# BMS_Main_RevC1.net
KiCad netlist of a schematic drawn in EAGLE
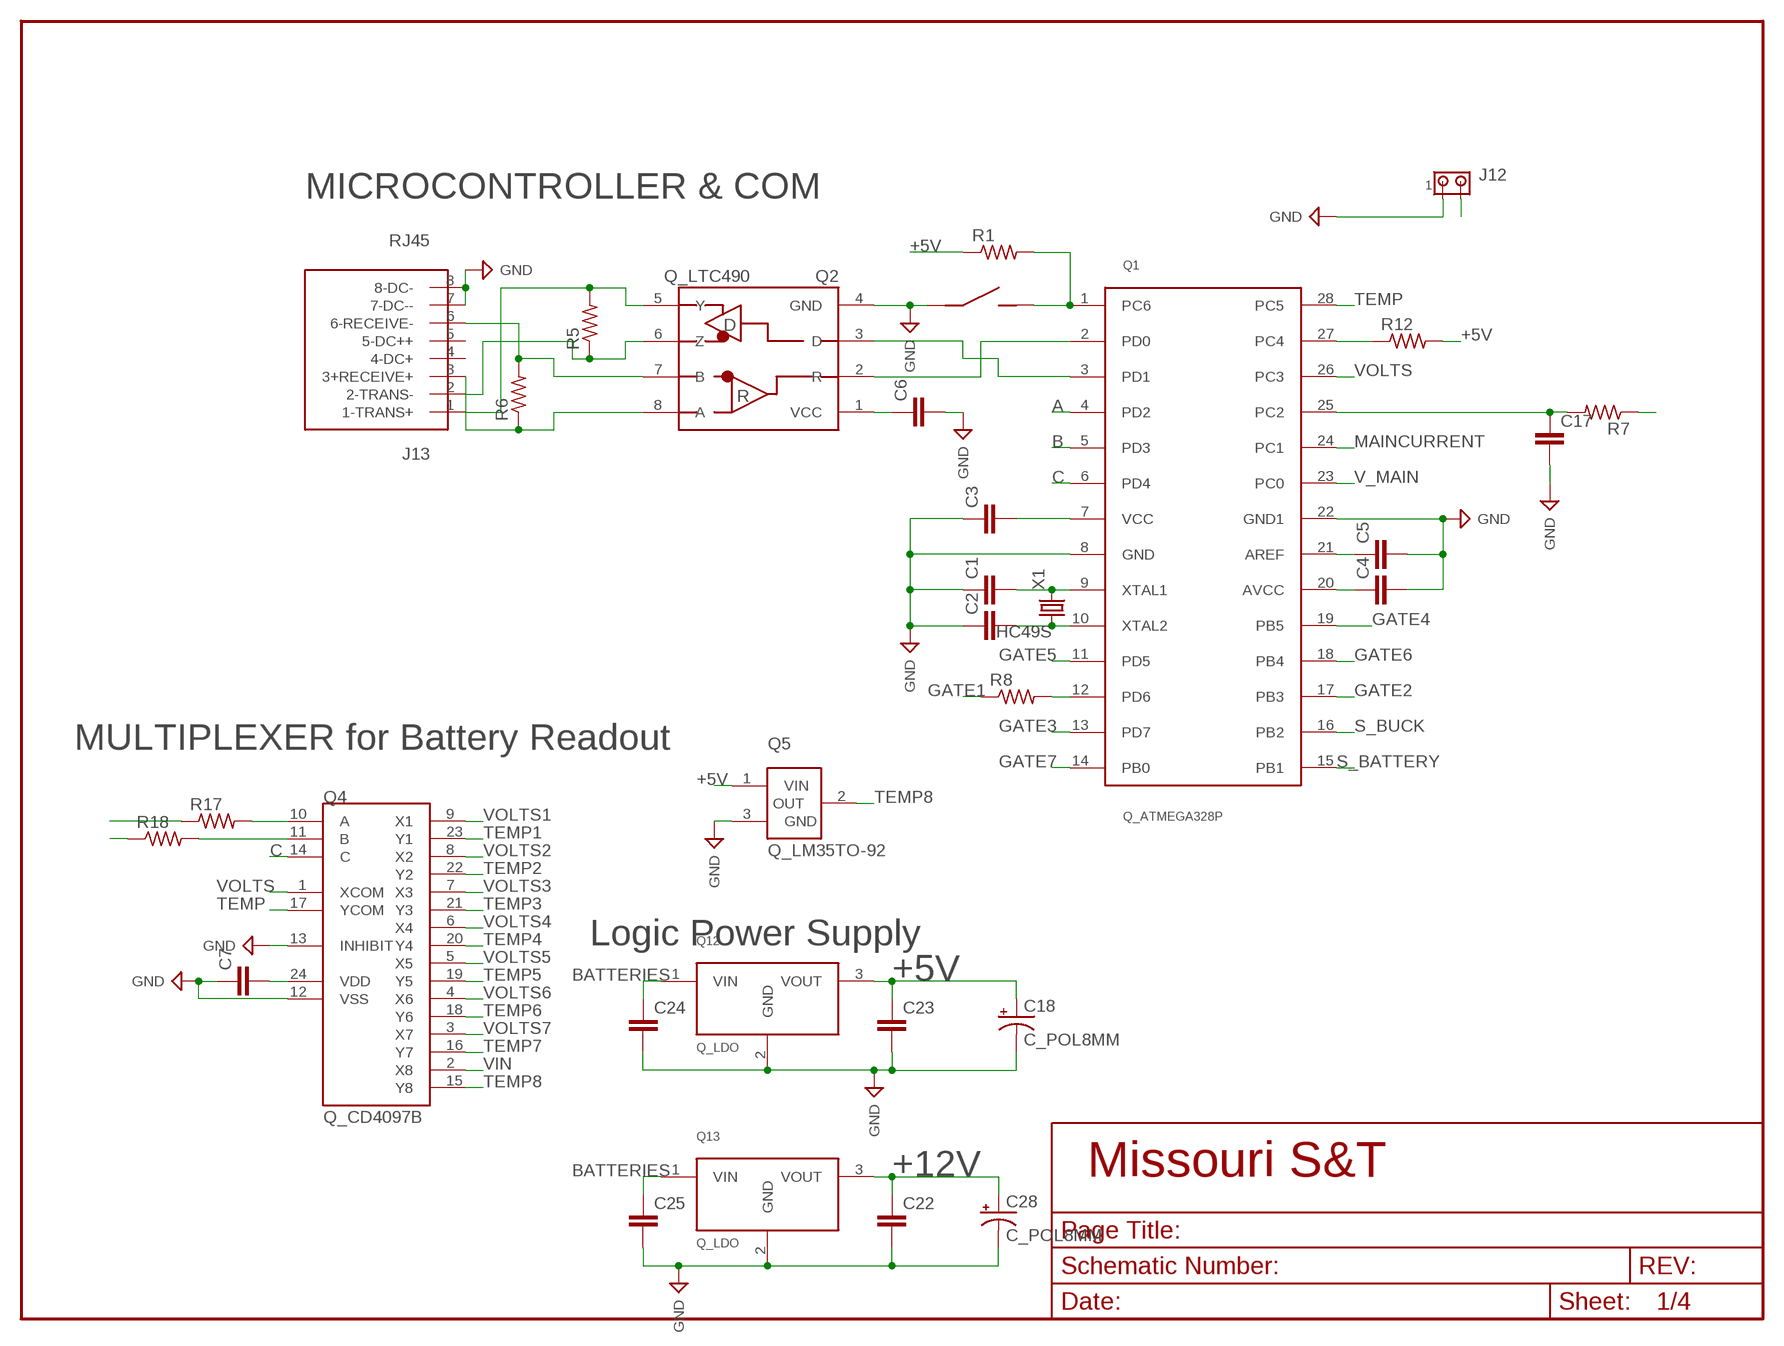
[diagram p0: schematic, sheet 1]
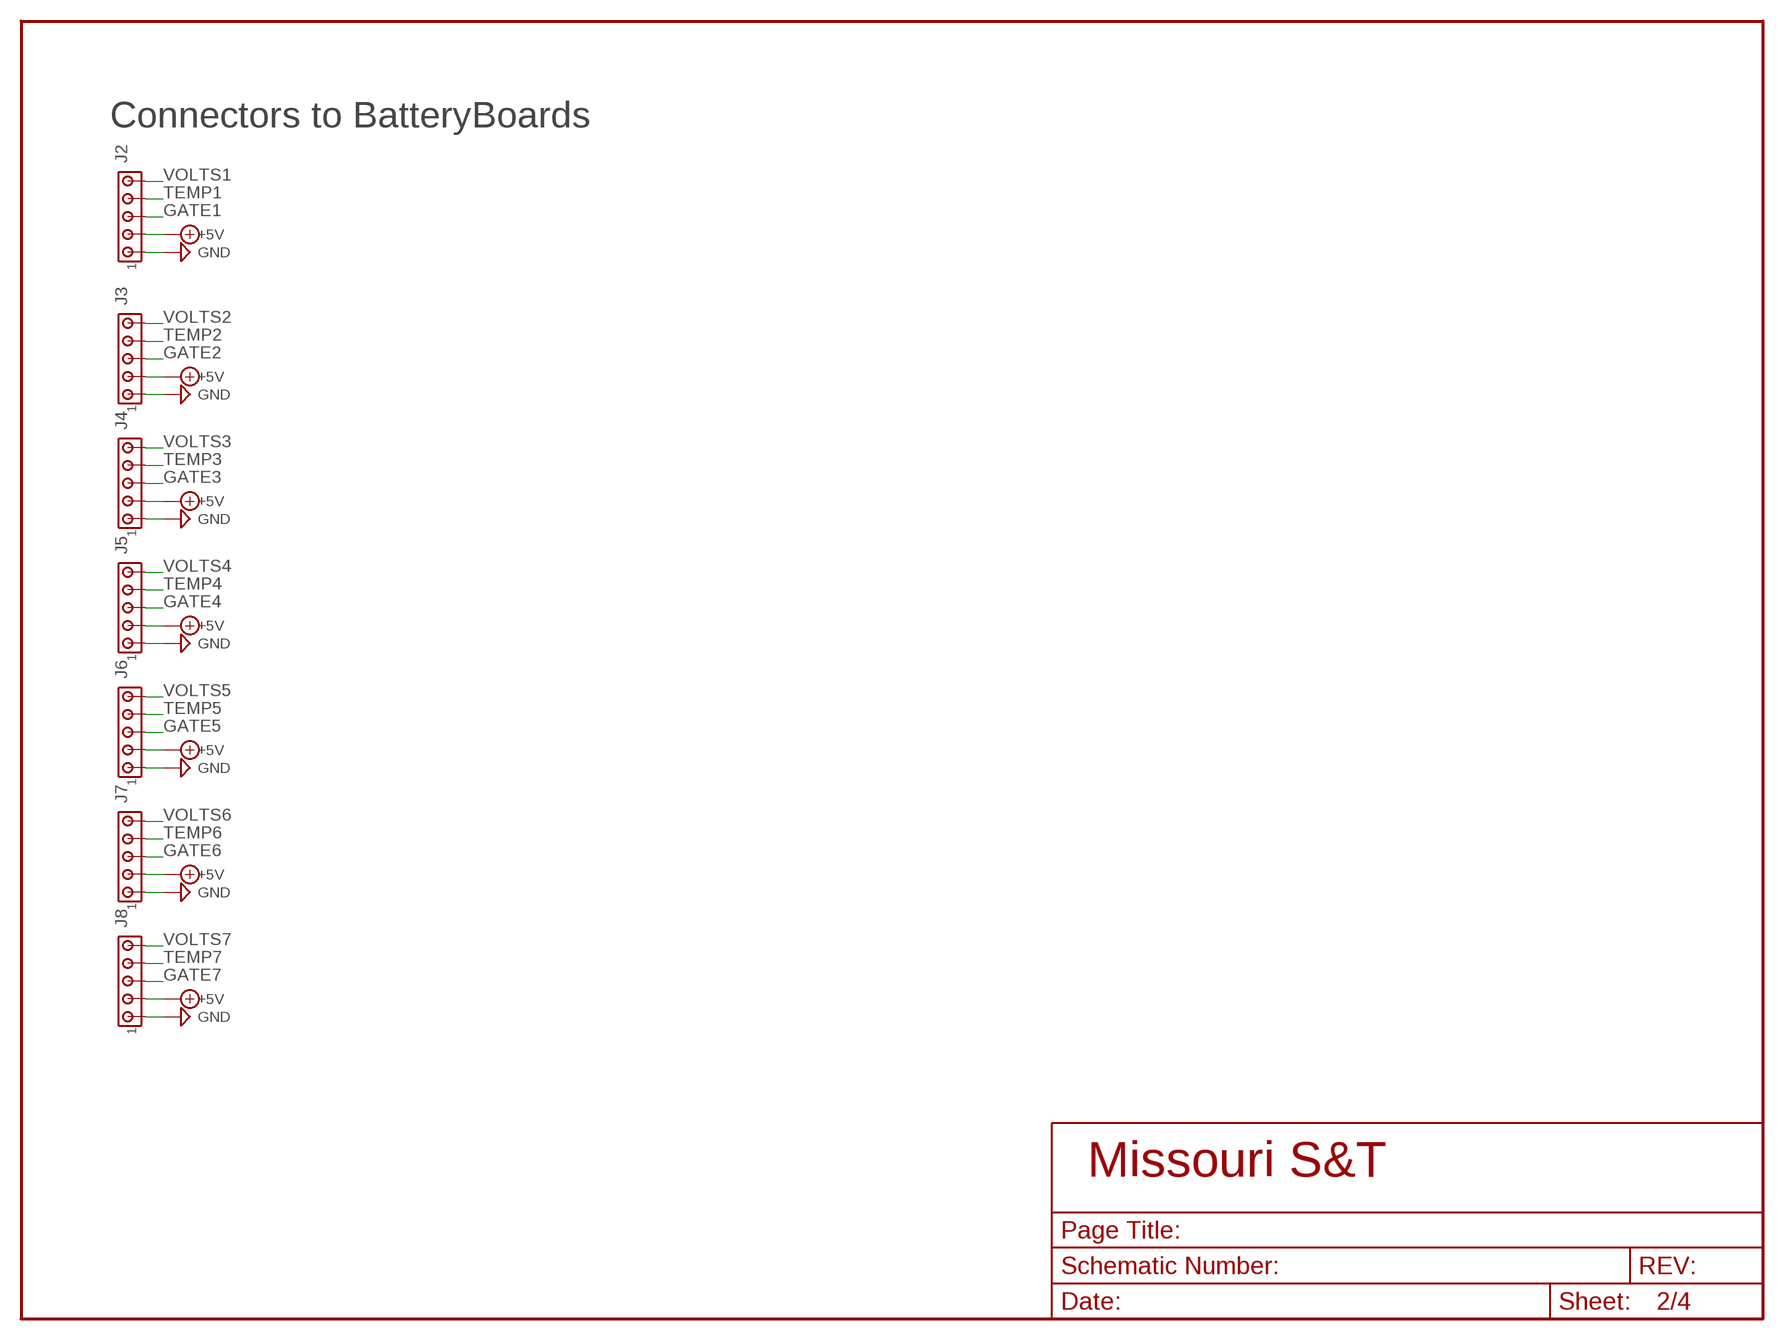
[diagram p1: schematic, sheet 2]
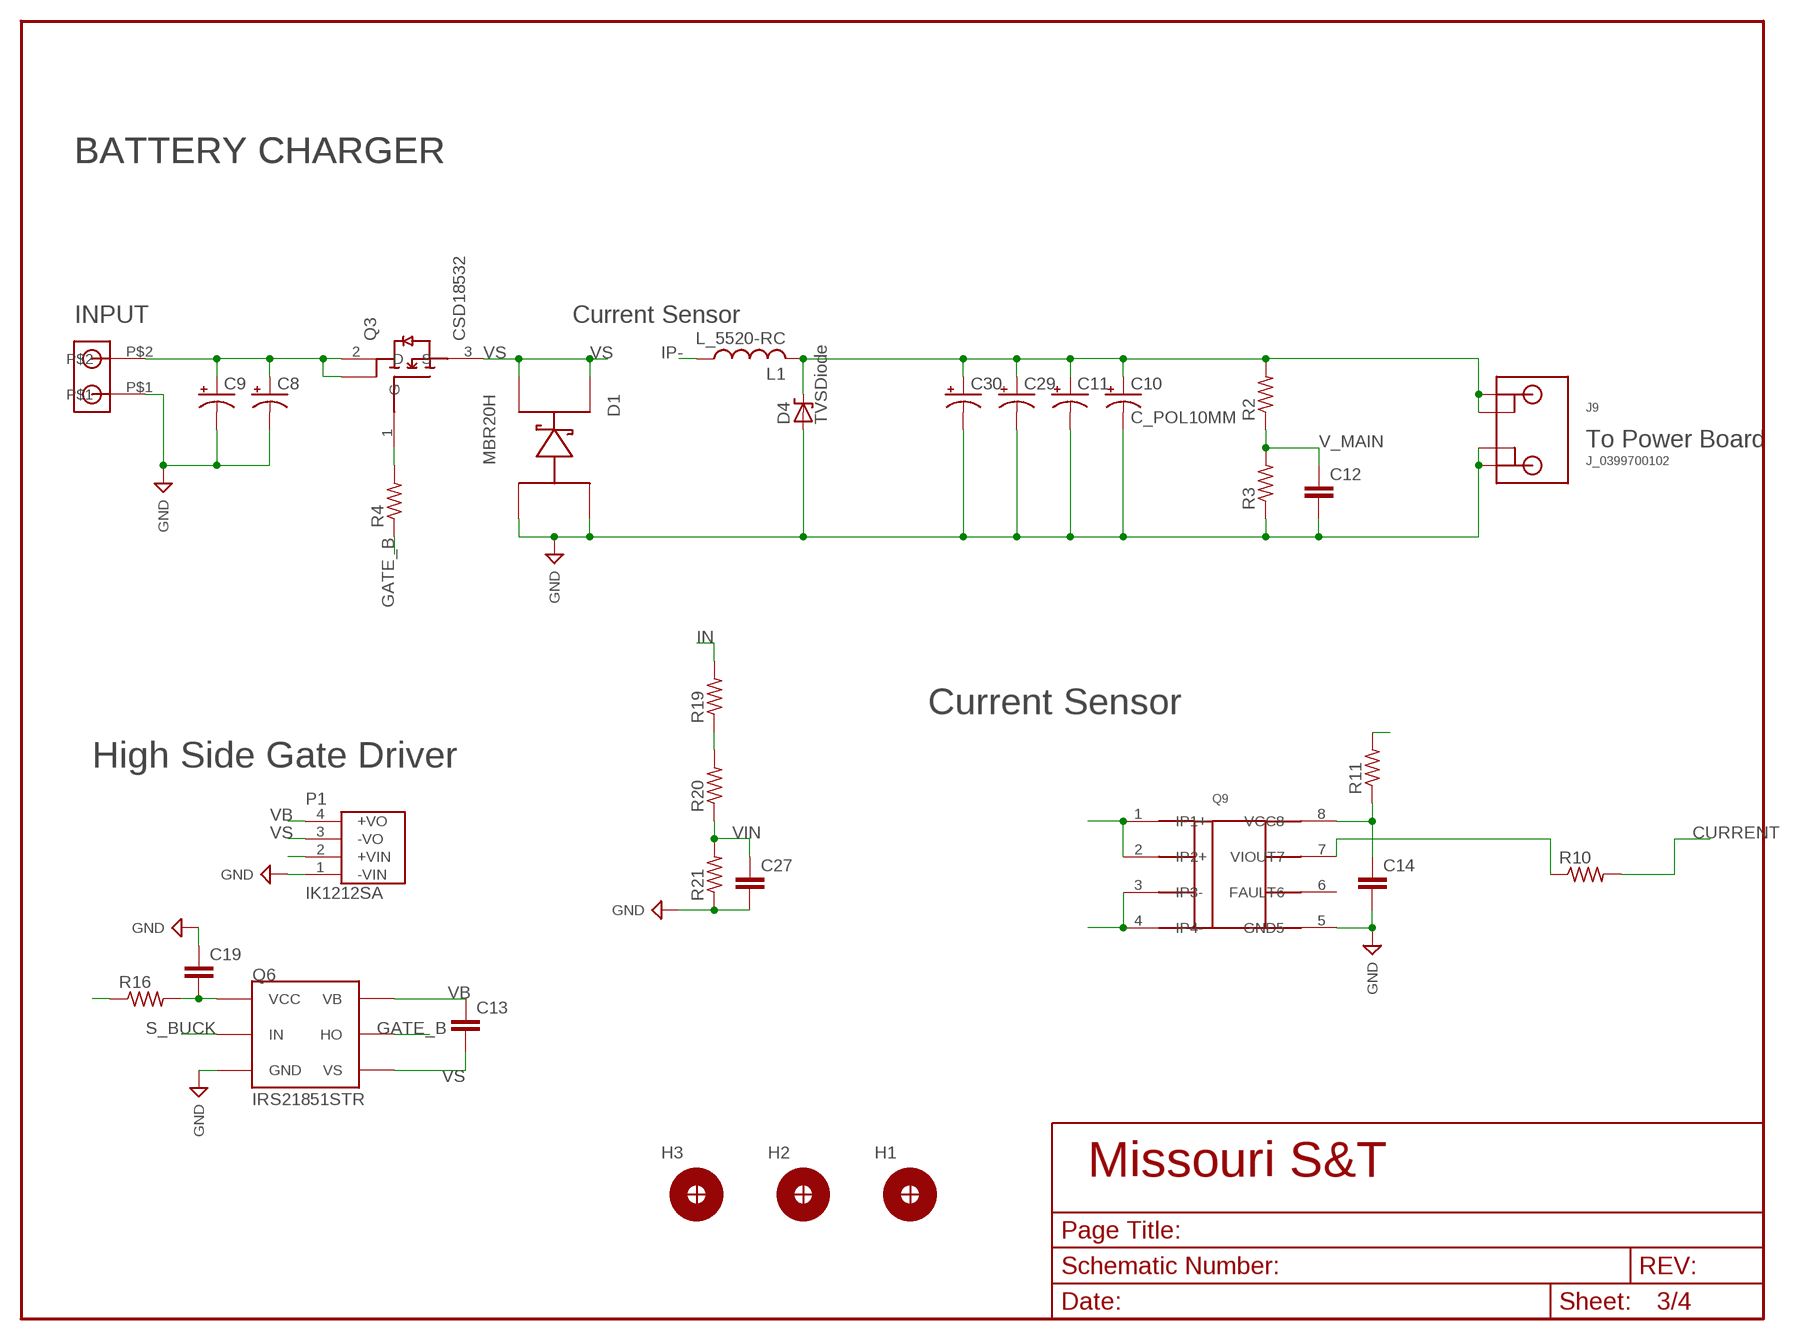
[diagram p2: schematic, sheet 3]
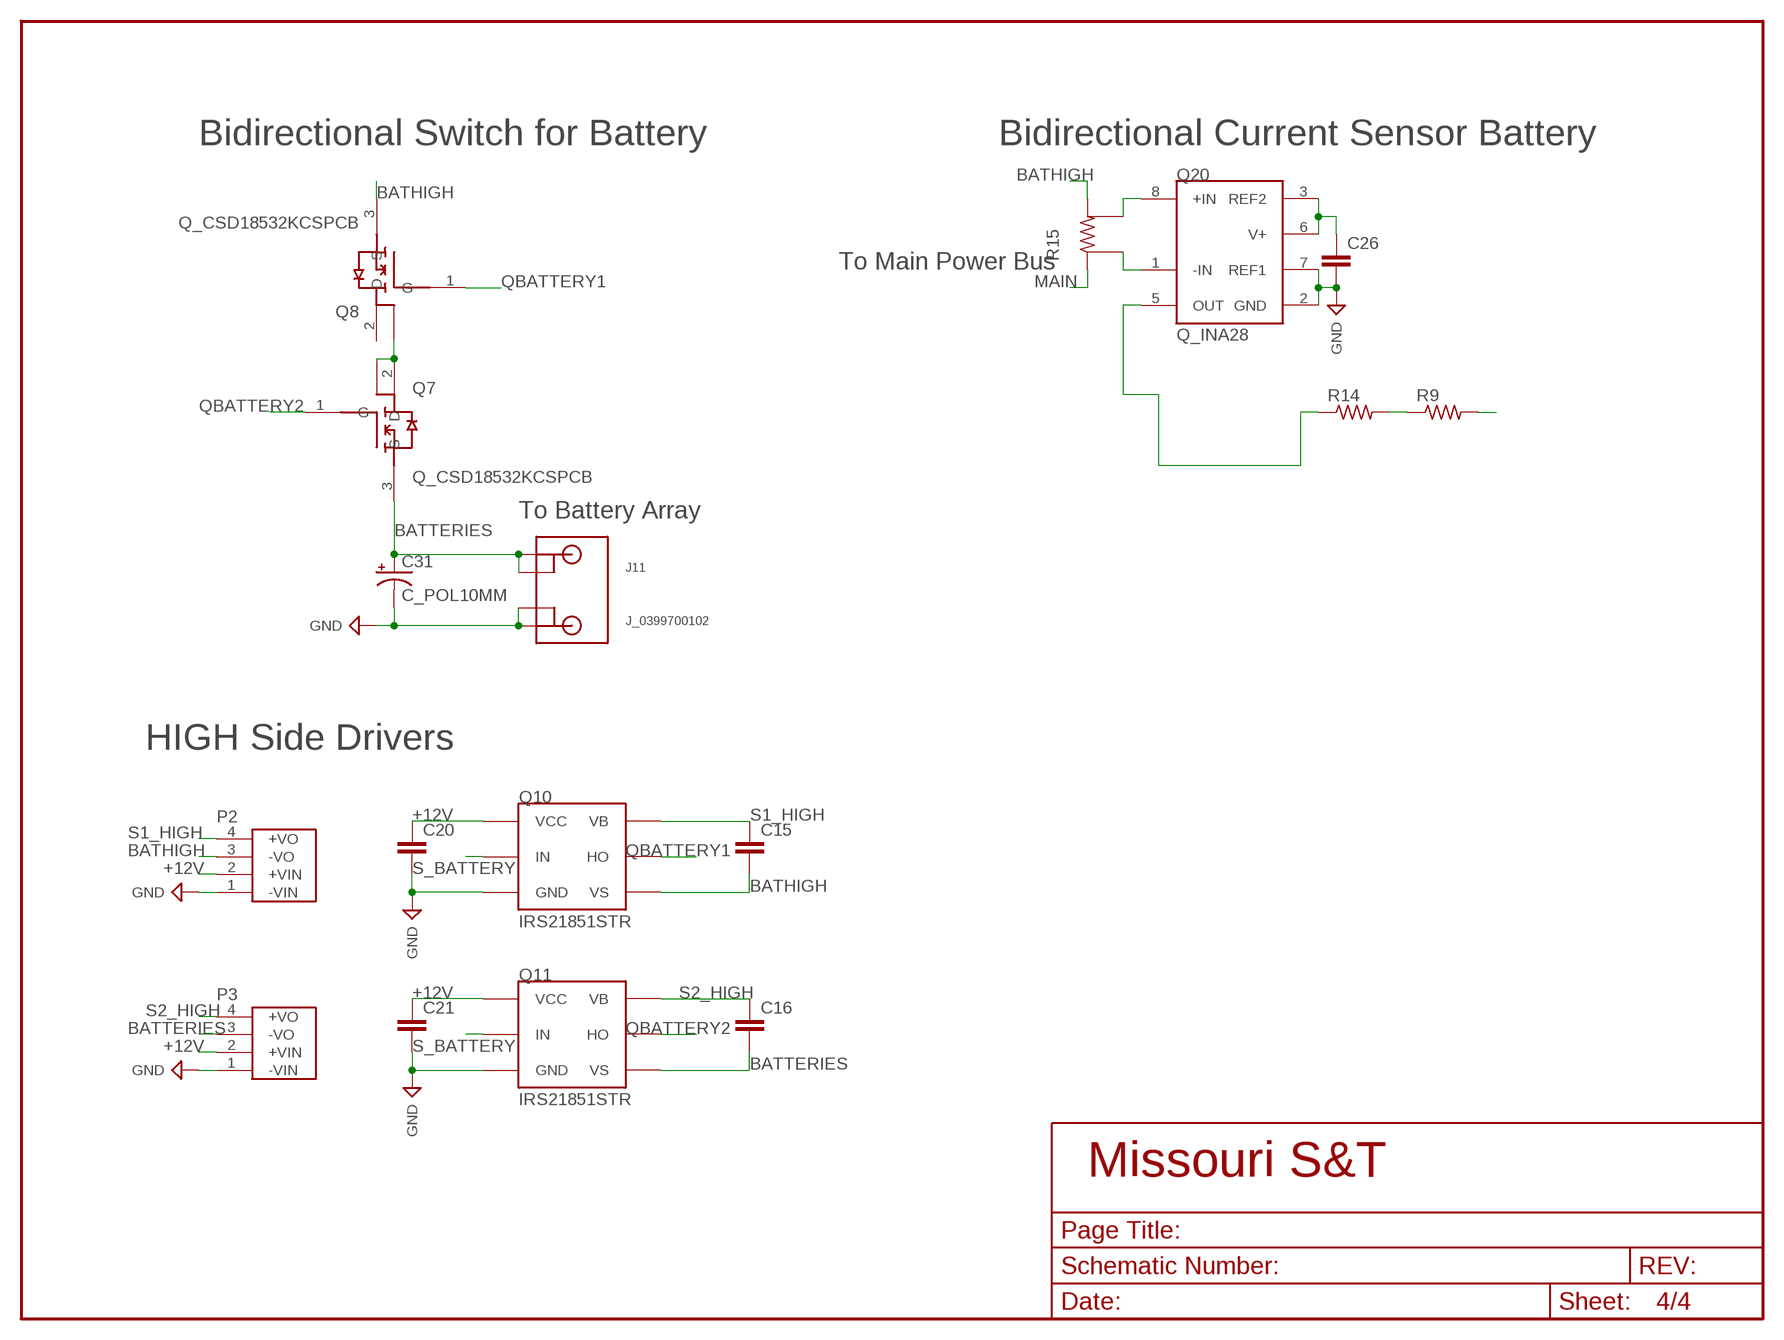
[diagram p3: schematic, sheet 4]

(export (version "E")
  (design (tool "Eeschema 10.0.6"))
  (components
    (comp (ref "C8")
      (value "C_POL10MM")
      (footprint "eagle-import:C_10MM")
      (libsource (lib "eagle-import") (part "C_POL10MM"))
    )
    (comp (ref "C9")
      (value "C_POL10MM")
      (footprint "eagle-import:C_10MM")
      (libsource (lib "eagle-import") (part "C_POL10MM"))
    )
    (comp (ref "C10")
      (value "C_POL10MM")
      (footprint "eagle-import:C_10MM")
      (libsource (lib "eagle-import") (part "C_POL10MM"))
    )
    (comp (ref "C11")
      (value "C_POL10MM")
      (footprint "eagle-import:C_10MM")
      (libsource (lib "eagle-import") (part "C_POL10MM"))
    )
    (comp (ref "C12")
      (value "C_CAP_1206")
      (footprint "eagle-import:C_1206")
      (libsource (lib "eagle-import") (part "C_CAP_1206"))
    )
    (comp (ref "C13")
      (value "C_CAP_1206")
      (footprint "eagle-import:C_1206")
      (libsource (lib "eagle-import") (part "C_CAP_1206"))
    )
    (comp (ref "C14")
      (value "C_CAP_1206")
      (footprint "eagle-import:C_1206")
      (libsource (lib "eagle-import") (part "C_CAP_1206"))
    )
    (comp (ref "C19")
      (value "C_CAP_1206")
      (footprint "eagle-import:C_1206")
      (libsource (lib "eagle-import") (part "C_CAP_1206"))
    )
    (comp (ref "C27")
      (value "C_CAP_1206")
      (footprint "eagle-import:C_1206")
      (libsource (lib "eagle-import") (part "C_CAP_1206"))
    )
    (comp (ref "C29")
      (value "C_POL10MM")
      (footprint "eagle-import:C_10MM")
      (libsource (lib "eagle-import") (part "C_POL10MM"))
    )
    (comp (ref "C30")
      (value "C_POL10MM")
      (footprint "eagle-import:C_10MM")
      (libsource (lib "eagle-import") (part "C_POL10MM"))
    )
    (comp (ref "D1")
      (value "MBR20H")
      (footprint "eagle-import:TO-220-FLAT")
      (libsource (lib "eagle-import") (part "D_MBR20H150CTG"))
    )
    (comp (ref "D4")
      (value "TVSDiode")
      (footprint "eagle-import:DIODE_D3.5MM_LS15.24MM")
      (libsource (lib "eagle-import") (part "D_1.5KE480A_D3.5MM_LS15.24MM"))
    )
    (comp (ref "H1")
      (value "H_MNTHOLE_#6")
      (footprint "eagle-import:H_MNTHOLE_#6")
      (libsource (lib "eagle-import") (part "H_MNTHOLE_#6"))
    )
    (comp (ref "H2")
      (value "H_MNTHOLE_#6")
      (footprint "eagle-import:H_MNTHOLE_#6")
      (libsource (lib "eagle-import") (part "H_MNTHOLE_#6"))
    )
    (comp (ref "H3")
      (value "H_MNTHOLE_#6")
      (footprint "eagle-import:H_MNTHOLE_#6")
      (libsource (lib "eagle-import") (part "H_MNTHOLE_#6"))
    )
    (comp (ref "J9")
      (value "J_0399700102")
      (footprint "eagle-import:J_2CONHC")
      (libsource (lib "eagle-import") (part "J_0399700102"))
    )
    (comp (ref "J10")
      (value "J_1546074-2")
      (footprint "eagle-import:THERM_BLOCK_2")
      (libsource (lib "eagle-import") (part "J_1546074-2"))
    )
    (comp (ref "L1")
      (value "L_5520-RC")
      (footprint "eagle-import:L_5520-RC")
      (libsource (lib "eagle-import") (part "L_5520-RC"))
    )
    (comp (ref "P1")
      (value "IK1212SA")
      (footprint "eagle-import:TME1215S")
      (libsource (lib "eagle-import") (part "TME1215S"))
    )
    (comp (ref "Q3")
      (value "CSD18532")
      (footprint "eagle-import:TO-220-FLAT")
      (libsource (lib "eagle-import") (part "Q_CSD18532KCSPCB"))
    )
    (comp (ref "Q6")
      (value "IRS21851STR")
      (footprint "eagle-import:SOIC8")
      (libsource (lib "eagle-import") (part "Q_IRS21851STR"))
    )
    (comp (ref "Q9")
      (value "Q_SO8ACS711")
      (footprint "eagle-import:Q_SO8")
      (libsource (lib "eagle-import") (part "Q_SO8ACS711"))
    )
    (comp (ref "R2")
      (value "R_1/4W")
      (footprint "eagle-import:R_1_4W")
      (libsource (lib "eagle-import") (part "R_1/4W"))
    )
    (comp (ref "R3")
      (value "R_RES_1206")
      (footprint "eagle-import:R_1206")
      (libsource (lib "eagle-import") (part "R_RES_1206"))
    )
    (comp (ref "R4")
      (value "R_RES_1206")
      (footprint "eagle-import:R_1206")
      (libsource (lib "eagle-import") (part "Lib_Passive - Copy_R_RES_1206"))
    )
    (comp (ref "R10")
      (value "R_1/4W")
      (footprint "eagle-import:R_1_4W")
      (libsource (lib "eagle-import") (part "R_1/4W"))
    )
    (comp (ref "R11")
      (value "R_1/4W")
      (footprint "eagle-import:R_1_4W")
      (libsource (lib "eagle-import") (part "R_1/4W"))
    )
    (comp (ref "R16")
      (value "R_1/4W")
      (footprint "eagle-import:R_1_4W")
      (libsource (lib "eagle-import") (part "R_1/4W"))
    )
    (comp (ref "R19")
      (value "R_1/4W")
      (footprint "eagle-import:R_1_4W")
      (libsource (lib "eagle-import") (part "R_1/4W"))
    )
    (comp (ref "R20")
      (value "R_1/4W")
      (footprint "eagle-import:R_1_4W")
      (libsource (lib "eagle-import") (part "R_1/4W"))
    )
    (comp (ref "R21")
      (value "R_RES_1206")
      (footprint "eagle-import:R_1206")
      (libsource (lib "eagle-import") (part "R_RES_1206"))
    )
    (comp (ref "C15")
      (value "C_CAP_1206")
      (footprint "eagle-import:C_1206")
      (libsource (lib "eagle-import") (part "C_CAP_1206"))
    )
    (comp (ref "C16")
      (value "C_CAP_1206")
      (footprint "eagle-import:C_1206")
      (libsource (lib "eagle-import") (part "C_CAP_1206"))
    )
    (comp (ref "C20")
      (value "C_CAP_1206")
      (footprint "eagle-import:C_1206")
      (libsource (lib "eagle-import") (part "C_CAP_1206"))
    )
    (comp (ref "C21")
      (value "C_CAP_1206")
      (footprint "eagle-import:C_1206")
      (libsource (lib "eagle-import") (part "C_CAP_1206"))
    )
    (comp (ref "C26")
      (value "C_CAP_1206")
      (footprint "eagle-import:C_1206")
      (libsource (lib "eagle-import") (part "C_CAP_1206"))
    )
    (comp (ref "C31")
      (value "C_POL10MM")
      (footprint "eagle-import:C_10MM")
      (libsource (lib "eagle-import") (part "C_POL10MM"))
    )
    (comp (ref "J11")
      (value "J_0399700102")
      (footprint "eagle-import:J_2CONHC")
      (libsource (lib "eagle-import") (part "J_0399700102"))
    )
    (comp (ref "P2")
      (value "TME1215S")
      (footprint "eagle-import:TME1215S")
      (libsource (lib "eagle-import") (part "TME1215S"))
    )
    (comp (ref "P3")
      (value "TME1215S")
      (footprint "eagle-import:TME1215S")
      (libsource (lib "eagle-import") (part "TME1215S"))
    )
    (comp (ref "Q7")
      (value "Q_CSD18532KCSPCB")
      (footprint "eagle-import:TO-220-FLAT")
      (libsource (lib "eagle-import") (part "Q_CSD18532KCSPCB"))
    )
    (comp (ref "Q8")
      (value "Q_CSD18532KCSPCB")
      (footprint "eagle-import:TO-220-FLAT")
      (libsource (lib "eagle-import") (part "Q_CSD18532KCSPCB"))
    )
    (comp (ref "Q10")
      (value "IRS21851STR")
      (footprint "eagle-import:SOIC8")
      (libsource (lib "eagle-import") (part "Q_IRS21851STR"))
    )
    (comp (ref "Q11")
      (value "IRS21851STR")
      (footprint "eagle-import:SOIC8")
      (libsource (lib "eagle-import") (part "Q_IRS21851STR"))
    )
    (comp (ref "Q20")
      (value "Q_INA28")
      (footprint "eagle-import:SOIC8")
      (libsource (lib "eagle-import") (part "Q_INA28"))
    )
    (comp (ref "R9")
      (value "R_1/4W")
      (footprint "eagle-import:R_1_4W")
      (libsource (lib "eagle-import") (part "R_1/4W"))
    )
    (comp (ref "R14")
      (value "R_1/4W")
      (footprint "eagle-import:R_1_4W")
      (libsource (lib "eagle-import") (part "R_1/4W"))
    )
    (comp (ref "R15")
      (value "R_FC4L110R001JER")
      (footprint "eagle-import:R_FC4L")
      (libsource (lib "eagle-import") (part "R_FC4L110R001JER"))
    )
    (comp (ref "J2")
      (value "J_MTA5P_100")
      (footprint "eagle-import:J_MTA100_5P")
      (libsource (lib "eagle-import") (part "J_MTA5P_100"))
    )
    (comp (ref "J3")
      (value "J_MTA5P_100")
      (footprint "eagle-import:J_MTA100_5P")
      (libsource (lib "eagle-import") (part "J_MTA5P_100"))
    )
    (comp (ref "J4")
      (value "J_MTA5P_100")
      (footprint "eagle-import:J_MTA100_5P")
      (libsource (lib "eagle-import") (part "J_MTA5P_100"))
    )
    (comp (ref "J5")
      (value "J_MTA5P_100")
      (footprint "eagle-import:J_MTA100_5P")
      (libsource (lib "eagle-import") (part "J_MTA5P_100"))
    )
    (comp (ref "J6")
      (value "J_MTA5P_100")
      (footprint "eagle-import:J_MTA100_5P")
      (libsource (lib "eagle-import") (part "J_MTA5P_100"))
    )
    (comp (ref "J7")
      (value "J_MTA5P_100")
      (footprint "eagle-import:J_MTA100_5P")
      (libsource (lib "eagle-import") (part "J_MTA5P_100"))
    )
    (comp (ref "J8")
      (value "J_MTA5P_100")
      (footprint "eagle-import:J_MTA100_5P")
      (libsource (lib "eagle-import") (part "J_MTA5P_100"))
    )
    (comp (ref "C1")
      (value "C_CAP_1206")
      (footprint "eagle-import:C_1206")
      (libsource (lib "eagle-import") (part "C_CAP_1206"))
    )
    (comp (ref "C2")
      (value "C_CAP_1206")
      (footprint "eagle-import:C_1206")
      (libsource (lib "eagle-import") (part "C_CAP_1206"))
    )
    (comp (ref "C3")
      (value "C_CAP_1206")
      (footprint "eagle-import:C_1206")
      (libsource (lib "eagle-import") (part "C_CAP_1206"))
    )
    (comp (ref "C4")
      (value "C_CAP_1206")
      (footprint "eagle-import:C_1206")
      (libsource (lib "eagle-import") (part "C_CAP_1206"))
    )
    (comp (ref "C5")
      (value "C_CAP_1206")
      (footprint "eagle-import:C_1206")
      (libsource (lib "eagle-import") (part "C_CAP_1206"))
    )
    (comp (ref "C6")
      (value "C_CAP_1206")
      (footprint "eagle-import:C_1206")
      (libsource (lib "eagle-import") (part "C_CAP_1206"))
    )
    (comp (ref "C7")
      (value "C_CAP_1206")
      (footprint "eagle-import:C_1206")
      (libsource (lib "eagle-import") (part "C_CAP_1206"))
    )
    (comp (ref "C17")
      (value "C_CAP_1206")
      (footprint "eagle-import:C_1206")
      (libsource (lib "eagle-import") (part "C_CAP_1206"))
    )
    (comp (ref "C18")
      (value "C_POL8MM")
      (footprint "eagle-import:C_8MM")
      (libsource (lib "eagle-import") (part "C_POL8MM"))
    )
    (comp (ref "C22")
      (value "C_CAP_1206")
      (footprint "eagle-import:C_1206")
      (libsource (lib "eagle-import") (part "C_CAP_1206"))
    )
    (comp (ref "C23")
      (value "C_CAP_1206")
      (footprint "eagle-import:C_1206")
      (libsource (lib "eagle-import") (part "C_CAP_1206"))
    )
    (comp (ref "C24")
      (value "C_CAP_1206")
      (footprint "eagle-import:C_1206")
      (libsource (lib "eagle-import") (part "C_CAP_1206"))
    )
    (comp (ref "C25")
      (value "C_CAP_1206")
      (footprint "eagle-import:C_1206")
      (libsource (lib "eagle-import") (part "C_CAP_1206"))
    )
    (comp (ref "C28")
      (value "C_POL8MM")
      (footprint "eagle-import:C_8MM")
      (libsource (lib "eagle-import") (part "C_POL8MM"))
    )
    (comp (ref "J1")
      (value "J_MC32857")
      (footprint "eagle-import:J_TOGGLE")
      (libsource (lib "eagle-import") (part "J_MC32857"))
    )
    (comp (ref "J12")
      (value "J_MTA2P_100")
      (footprint "eagle-import:J_MTA100_2P")
      (libsource (lib "eagle-import") (part "J_MTA2P_100"))
    )
    (comp (ref "J13")
      (value "RJ45")
      (footprint "eagle-import:RJ45-CAT5E")
      (libsource (lib "eagle-import") (part "RJ45"))
    )
    (comp (ref "Q1")
      (value "Q_ATMEGA328P")
      (footprint "eagle-import:DIP28")
      (libsource (lib "eagle-import") (part "Q_ATMEGA328P"))
    )
    (comp (ref "Q2")
      (value "Q_LTC490")
      (footprint "eagle-import:DIP8")
      (libsource (lib "eagle-import") (part "Q_LTC490"))
    )
    (comp (ref "Q4")
      (value "Q_CD4097B")
      (footprint "eagle-import:WDIP24")
      (libsource (lib "eagle-import") (part "Q_CD4067BRIGHT"))
    )
    (comp (ref "Q5")
      (value "Q_LM35TO-92")
      (footprint "eagle-import:TO-92-3")
      (libsource (lib "eagle-import") (part "Q_LM35TO-92"))
    )
    (comp (ref "Q12")
      (value "Q_LDO")
      (footprint "eagle-import:TO-220")
      (libsource (lib "eagle-import") (part "Q_LDO"))
    )
    (comp (ref "Q13")
      (value "Q_LDO")
      (footprint "eagle-import:TO-220")
      (libsource (lib "eagle-import") (part "Q_LDO"))
    )
    (comp (ref "R1")
      (value "R_RES_1206")
      (footprint "eagle-import:R_1206")
      (libsource (lib "eagle-import") (part "R_RES_1206"))
    )
    (comp (ref "R5")
      (value "R_RES_1206")
      (footprint "eagle-import:R_1206")
      (libsource (lib "eagle-import") (part "Lib_Passive - Copy_R_RES_1206"))
    )
    (comp (ref "R6")
      (value "R_RES_1206")
      (footprint "eagle-import:R_1206")
      (libsource (lib "eagle-import") (part "Lib_Passive - Copy_R_RES_1206"))
    )
    (comp (ref "R7")
      (value "R_1/4W")
      (footprint "eagle-import:R_1_4W")
      (libsource (lib "eagle-import") (part "R_1/4W"))
    )
    (comp (ref "R8")
      (value "R_1/4W")
      (footprint "eagle-import:R_1_4W")
      (libsource (lib "eagle-import") (part "R_1/4W"))
    )
    (comp (ref "R12")
      (value "R_RES_0805")
      (footprint "eagle-import:R_0805")
      (libsource (lib "eagle-import") (part "R_RES_0805"))
    )
    (comp (ref "R17")
      (value "R_1/4W")
      (footprint "eagle-import:R_1_4W")
      (libsource (lib "eagle-import") (part "R_1/4W"))
    )
    (comp (ref "R18")
      (value "R_1/4W")
      (footprint "eagle-import:R_1_4W")
      (libsource (lib "eagle-import") (part "R_1/4W"))
    )
    (comp (ref "X1")
      (value "HC49S")
      (footprint "eagle-import:HC-49")
      (libsource (lib "eagle-import") (part "X_HC49SCRYSTAL"))
    )
  )
  (nets
    (net (code "1") (name "+5V") (class "Default")
      (node (ref "C18") (pin "+") (pinfunction "+_+") (pintype "passive"))
      (node (ref "C23") (pin "1") (pinfunction "1_1") (pintype "passive"))
      (node (ref "C3") (pin "2") (pinfunction "2_2") (pintype "passive"))
      (node (ref "C4") (pin "1") (pinfunction "1_1") (pintype "passive"))
      (node (ref "C6") (pin "1") (pinfunction "1_1") (pintype "passive"))
      (node (ref "C7") (pin "2") (pinfunction "2_2") (pintype "passive"))
      (node (ref "J2") (pin "2") (pinfunction "2_2") (pintype "passive"))
      (node (ref "J3") (pin "2") (pinfunction "2_2") (pintype "passive"))
      (node (ref "J4") (pin "2") (pinfunction "2_2") (pintype "passive"))
      (node (ref "J5") (pin "2") (pinfunction "2_2") (pintype "passive"))
      (node (ref "J6") (pin "2") (pinfunction "2_2") (pintype "passive"))
      (node (ref "J7") (pin "2") (pinfunction "2_2") (pintype "passive"))
      (node (ref "J8") (pin "2") (pinfunction "2_2") (pintype "passive"))
      (node (ref "Q1") (pin "20") (pinfunction "AVCC_20") (pintype "bidirectional"))
      (node (ref "Q1") (pin "7") (pinfunction "VCC_7") (pintype "bidirectional"))
      (node (ref "Q12") (pin "3") (pinfunction "VOUT_3") (pintype "bidirectional"))
      (node (ref "Q2") (pin "1") (pinfunction "VCC_1") (pintype "bidirectional"))
      (node (ref "Q4") (pin "24") (pinfunction "VDD_24") (pintype "bidirectional"))
      (node (ref "Q5") (pin "1") (pinfunction "VIN_1") (pintype "bidirectional"))
      (node (ref "R1") (pin "1") (pinfunction "1_1") (pintype "passive"))
      (node (ref "R11") (pin "2") (pinfunction "2_2") (pintype "passive"))
      (node (ref "R12") (pin "2") (pinfunction "2_2") (pintype "passive"))
    )
    (net (code "2") (name "+5V1") (class "Default")
      (node (ref "C14") (pin "1") (pinfunction "1_1") (pintype "passive"))
      (node (ref "C26") (pin "1") (pinfunction "1_1") (pintype "passive"))
      (node (ref "Q20") (pin "3") (pinfunction "REF2_3") (pintype "bidirectional"))
      (node (ref "Q20") (pin "6") (pinfunction "V+_6") (pintype "bidirectional"))
      (node (ref "Q9") (pin "8") (pinfunction "VCC8_8") (pintype "bidirectional"))
      (node (ref "R11") (pin "1") (pinfunction "1_1") (pintype "passive"))
    )
    (net (code "3") (name "+12V") (class "Default")
      (node (ref "C20") (pin "1") (pinfunction "1_1") (pintype "passive"))
      (node (ref "C21") (pin "1") (pinfunction "1_1") (pintype "passive"))
      (node (ref "C22") (pin "1") (pinfunction "1_1") (pintype "passive"))
      (node (ref "C28") (pin "+") (pinfunction "+_+") (pintype "passive"))
      (node (ref "P2") (pin "2") (pinfunction "+VIN_2") (pintype "input"))
      (node (ref "P3") (pin "2") (pinfunction "+VIN_2") (pintype "input"))
      (node (ref "Q10") (pin "1") (pinfunction "VCC_1") (pintype "bidirectional"))
      (node (ref "Q11") (pin "1") (pinfunction "VCC_1") (pintype "bidirectional"))
      (node (ref "Q13") (pin "3") (pinfunction "VOUT_3") (pintype "bidirectional"))
      (node (ref "R16") (pin "1") (pinfunction "1_1") (pintype "passive"))
    )
    (net (code "4") (name "+12V1") (class "Default")
      (node (ref "C19") (pin "2") (pinfunction "2_2") (pintype "passive"))
      (node (ref "P1") (pin "2") (pinfunction "+VIN_2") (pintype "input"))
      (node (ref "Q6") (pin "1") (pinfunction "VCC_1") (pintype "bidirectional"))
      (node (ref "R16") (pin "2") (pinfunction "2_2") (pintype "passive"))
    )
    (net (code "5") (name "A") (class "Default")
      (node (ref "Q1") (pin "4") (pinfunction "PD2_4") (pintype "bidirectional"))
      (node (ref "R17") (pin "1") (pinfunction "1_1") (pintype "passive"))
    )
    (net (code "6") (name "B") (class "Default")
      (node (ref "Q1") (pin "5") (pinfunction "PD3_5") (pintype "bidirectional"))
      (node (ref "R18") (pin "1") (pinfunction "1_1") (pintype "passive"))
    )
    (net (code "7") (name "BATHIGH") (class "Default")
      (node (ref "C15") (pin "2") (pinfunction "2_2") (pintype "passive"))
      (node (ref "P2") (pin "3") (pinfunction "-VO_3") (pintype "output"))
      (node (ref "Q10") (pin "6") (pinfunction "VS_6") (pintype "bidirectional"))
      (node (ref "Q8") (pin "3") (pinfunction "S_3") (pintype "bidirectional"))
      (node (ref "R15") (pin "2") (pinfunction "2_2") (pintype "passive"))
    )
    (net (code "8") (name "BATTERIES") (class "Default")
      (node (ref "C16") (pin "2") (pinfunction "2_2") (pintype "passive"))
      (node (ref "C24") (pin "1") (pinfunction "1_1") (pintype "passive"))
      (node (ref "C25") (pin "1") (pinfunction "1_1") (pintype "passive"))
      (node (ref "C31") (pin "P$1") (pinfunction "+_P$1") (pintype "passive"))
      (node (ref "J11") (pin "PIN1-1") (pinfunction "1-1_PIN1-1") (pintype "bidirectional"))
      (node (ref "J11") (pin "PIN1-2") (pinfunction "1-2_PIN1-2") (pintype "bidirectional"))
      (node (ref "P3") (pin "3") (pinfunction "-VO_3") (pintype "output"))
      (node (ref "Q11") (pin "6") (pinfunction "VS_6") (pintype "bidirectional"))
      (node (ref "Q12") (pin "1") (pinfunction "VIN_1") (pintype "bidirectional"))
      (node (ref "Q13") (pin "1") (pinfunction "VIN_1") (pintype "bidirectional"))
      (node (ref "Q7") (pin "3") (pinfunction "S_3") (pintype "bidirectional"))
    )
    (net (code "9") (name "C") (class "Default")
      (node (ref "Q1") (pin "6") (pinfunction "PD4_6") (pintype "bidirectional"))
      (node (ref "Q4") (pin "14") (pinfunction "C_14") (pintype "bidirectional"))
    )
    (net (code "10") (name "CURRENT") (class "Default")
      (node (ref "R10") (pin "2") (pinfunction "2_2") (pintype "passive"))
      (node (ref "R7") (pin "1") (pinfunction "1_1") (pintype "passive"))
    )
    (net (code "11") (name "GATE1") (class "Default")
      (node (ref "J2") (pin "3") (pinfunction "3_3") (pintype "passive"))
      (node (ref "R8") (pin "1") (pinfunction "1_1") (pintype "passive"))
    )
    (net (code "12") (name "GATE2") (class "Default")
      (node (ref "J3") (pin "3") (pinfunction "3_3") (pintype "passive"))
      (node (ref "Q1") (pin "17") (pinfunction "PB3_17") (pintype "bidirectional"))
    )
    (net (code "13") (name "GATE3") (class "Default")
      (node (ref "J4") (pin "3") (pinfunction "3_3") (pintype "passive"))
      (node (ref "Q1") (pin "13") (pinfunction "PD7_13") (pintype "bidirectional"))
    )
    (net (code "14") (name "GATE4") (class "Default")
      (node (ref "J5") (pin "3") (pinfunction "3_3") (pintype "passive"))
      (node (ref "Q1") (pin "19") (pinfunction "PB5_19") (pintype "bidirectional"))
    )
    (net (code "15") (name "GATE5") (class "Default")
      (node (ref "J6") (pin "3") (pinfunction "3_3") (pintype "passive"))
      (node (ref "Q1") (pin "11") (pinfunction "PD5_11") (pintype "bidirectional"))
    )
    (net (code "16") (name "GATE6") (class "Default")
      (node (ref "J7") (pin "3") (pinfunction "3_3") (pintype "passive"))
      (node (ref "Q1") (pin "18") (pinfunction "PB4_18") (pintype "bidirectional"))
    )
    (net (code "17") (name "GATE7") (class "Default")
      (node (ref "J8") (pin "3") (pinfunction "3_3") (pintype "passive"))
      (node (ref "Q1") (pin "14") (pinfunction "PB0_14") (pintype "bidirectional"))
    )
    (net (code "18") (name "GATE_B") (class "Default")
      (node (ref "Q6") (pin "7") (pinfunction "HO_7") (pintype "bidirectional"))
      (node (ref "R4") (pin "1") (pinfunction "1_1") (pintype "passive"))
    )
    (net (code "19") (name "GND") (class "Default")
      (node (ref "C1") (pin "1") (pinfunction "1_1") (pintype "passive"))
      (node (ref "C10") (pin "P$2") (pinfunction "-_P$2") (pintype "passive"))
      (node (ref "C11") (pin "P$2") (pinfunction "-_P$2") (pintype "passive"))
      (node (ref "C12") (pin "2") (pinfunction "2_2") (pintype "passive"))
      (node (ref "C14") (pin "2") (pinfunction "2_2") (pintype "passive"))
      (node (ref "C17") (pin "2") (pinfunction "2_2") (pintype "passive"))
      (node (ref "C18") (pin "-") (pinfunction "-_-") (pintype "passive"))
      (node (ref "C19") (pin "1") (pinfunction "1_1") (pintype "passive"))
      (node (ref "C2") (pin "1") (pinfunction "1_1") (pintype "passive"))
      (node (ref "C20") (pin "2") (pinfunction "2_2") (pintype "passive"))
      (node (ref "C21") (pin "2") (pinfunction "2_2") (pintype "passive"))
      (node (ref "C22") (pin "2") (pinfunction "2_2") (pintype "passive"))
      (node (ref "C23") (pin "2") (pinfunction "2_2") (pintype "passive"))
      (node (ref "C24") (pin "2") (pinfunction "2_2") (pintype "passive"))
      (node (ref "C25") (pin "2") (pinfunction "2_2") (pintype "passive"))
      (node (ref "C26") (pin "2") (pinfunction "2_2") (pintype "passive"))
      (node (ref "C27") (pin "2") (pinfunction "2_2") (pintype "passive"))
      (node (ref "C28") (pin "-") (pinfunction "-_-") (pintype "passive"))
      (node (ref "C29") (pin "P$2") (pinfunction "-_P$2") (pintype "passive"))
      (node (ref "C3") (pin "1") (pinfunction "1_1") (pintype "passive"))
      (node (ref "C30") (pin "P$2") (pinfunction "-_P$2") (pintype "passive"))
      (node (ref "C31") (pin "P$2") (pinfunction "-_P$2") (pintype "passive"))
      (node (ref "C4") (pin "2") (pinfunction "2_2") (pintype "passive"))
      (node (ref "C5") (pin "2") (pinfunction "2_2") (pintype "passive"))
      (node (ref "C6") (pin "2") (pinfunction "2_2") (pintype "passive"))
      (node (ref "C7") (pin "1") (pinfunction "1_1") (pintype "passive"))
      (node (ref "C8") (pin "P$2") (pinfunction "-_P$2") (pintype "passive"))
      (node (ref "C9") (pin "P$2") (pinfunction "-_P$2") (pintype "passive"))
      (node (ref "D1") (pin "1") (pinfunction "A1_1") (pintype "bidirectional"))
      (node (ref "D1") (pin "3") (pinfunction "A2_3") (pintype "bidirectional"))
      (node (ref "D4") (pin "A") (pinfunction "A_A") (pintype "passive"))
      (node (ref "J1") (pin "P$1") (pinfunction "1_P$1") (pintype "bidirectional"))
      (node (ref "J10") (pin "P$1") (pinfunction "P$1_P$1") (pintype "bidirectional"))
      (node (ref "J11") (pin "PIN2-1") (pinfunction "2-1_PIN2-1") (pintype "bidirectional"))
      (node (ref "J11") (pin "PIN2-2") (pinfunction "2-2_PIN2-2") (pintype "bidirectional"))
      (node (ref "J12") (pin "1") (pinfunction "1_1") (pintype "passive"))
      (node (ref "J13") (pin "7") (pinfunction "7-DC--_7") (pintype "bidirectional"))
      (node (ref "J13") (pin "8") (pinfunction "8-DC-_8") (pintype "bidirectional"))
      (node (ref "J2") (pin "1") (pinfunction "1_1") (pintype "passive"))
      (node (ref "J3") (pin "1") (pinfunction "1_1") (pintype "passive"))
      (node (ref "J4") (pin "1") (pinfunction "1_1") (pintype "passive"))
      (node (ref "J5") (pin "1") (pinfunction "1_1") (pintype "passive"))
      (node (ref "J6") (pin "1") (pinfunction "1_1") (pintype "passive"))
      (node (ref "J7") (pin "1") (pinfunction "1_1") (pintype "passive"))
      (node (ref "J8") (pin "1") (pinfunction "1_1") (pintype "passive"))
      (node (ref "J9") (pin "PIN2-1") (pinfunction "2-1_PIN2-1") (pintype "bidirectional"))
      (node (ref "J9") (pin "PIN2-2") (pinfunction "2-2_PIN2-2") (pintype "bidirectional"))
      (node (ref "P1") (pin "1") (pinfunction "-VIN_1") (pintype "input"))
      (node (ref "P2") (pin "1") (pinfunction "-VIN_1") (pintype "input"))
      (node (ref "P3") (pin "1") (pinfunction "-VIN_1") (pintype "input"))
      (node (ref "Q1") (pin "22") (pinfunction "GND1_22") (pintype "bidirectional"))
      (node (ref "Q1") (pin "8") (pinfunction "GND_8") (pintype "bidirectional"))
      (node (ref "Q10") (pin "4") (pinfunction "GND_4") (pintype "bidirectional"))
      (node (ref "Q11") (pin "4") (pinfunction "GND_4") (pintype "bidirectional"))
      (node (ref "Q12") (pin "2") (pinfunction "GND_2") (pintype "bidirectional"))
      (node (ref "Q13") (pin "2") (pinfunction "GND_2") (pintype "bidirectional"))
      (node (ref "Q2") (pin "4") (pinfunction "GND_4") (pintype "bidirectional"))
      (node (ref "Q20") (pin "2") (pinfunction "GND_2") (pintype "bidirectional"))
      (node (ref "Q20") (pin "7") (pinfunction "REF1_7") (pintype "bidirectional"))
      (node (ref "Q4") (pin "12") (pinfunction "VSS_12") (pintype "bidirectional"))
      (node (ref "Q4") (pin "13") (pinfunction "INHIBIT_13") (pintype "bidirectional"))
      (node (ref "Q5") (pin "3") (pinfunction "GND_3") (pintype "bidirectional"))
      (node (ref "Q6") (pin "4") (pinfunction "GND_4") (pintype "bidirectional"))
      (node (ref "Q9") (pin "5") (pinfunction "GND5_5") (pintype "bidirectional"))
      (node (ref "R21") (pin "1") (pinfunction "1_1") (pintype "passive"))
      (node (ref "R3") (pin "1") (pinfunction "1_1") (pintype "passive"))
    )
    (net (code "20") (name "IN") (class "Default")
      (node (ref "C8") (pin "P$1") (pinfunction "+_P$1") (pintype "passive"))
      (node (ref "C9") (pin "P$1") (pinfunction "+_P$1") (pintype "passive"))
      (node (ref "J10") (pin "P$2") (pinfunction "P$2_P$2") (pintype "bidirectional"))
      (node (ref "Q3") (pin "2") (pinfunction "D_2") (pintype "bidirectional"))
      (node (ref "Q3") (pin "4") (pinfunction "P$1_4") (pintype "bidirectional"))
      (node (ref "R19") (pin "2") (pinfunction "2_2") (pintype "passive"))
    )
    (net (code "21") (name "IP-") (class "Default")
      (node (ref "L1") (pin "1") (pinfunction "1_1") (pintype "passive"))
      (node (ref "Q9") (pin "1") (pinfunction "IP1+_1") (pintype "bidirectional"))
      (node (ref "Q9") (pin "2") (pinfunction "IP2+_2") (pintype "bidirectional"))
    )
    (net (code "22") (name "MAIN") (class "Default")
      (node (ref "C10") (pin "P$1") (pinfunction "+_P$1") (pintype "passive"))
      (node (ref "C11") (pin "P$1") (pinfunction "+_P$1") (pintype "passive"))
      (node (ref "C29") (pin "P$1") (pinfunction "+_P$1") (pintype "passive"))
      (node (ref "C30") (pin "P$1") (pinfunction "+_P$1") (pintype "passive"))
      (node (ref "D4") (pin "C") (pinfunction "K_C") (pintype "passive"))
      (node (ref "J9") (pin "PIN1-1") (pinfunction "1-1_PIN1-1") (pintype "bidirectional"))
      (node (ref "J9") (pin "PIN1-2") (pinfunction "1-2_PIN1-2") (pintype "bidirectional"))
      (node (ref "L1") (pin "2") (pinfunction "2_2") (pintype "passive"))
      (node (ref "R15") (pin "1") (pinfunction "1_1") (pintype "passive"))
      (node (ref "R2") (pin "2") (pinfunction "2_2") (pintype "passive"))
    )
    (net (code "23") (name "MAINCURRENT") (class "Default")
      (node (ref "Q1") (pin "24") (pinfunction "PC1_24") (pintype "bidirectional"))
      (node (ref "R9") (pin "2") (pinfunction "2_2") (pintype "passive"))
    )
    (net (code "24") (name "Net-(J1-2)") (class "Default")
      (node (ref "J1") (pin "P$2") (pinfunction "2_P$2") (pintype "bidirectional"))
      (node (ref "Q1") (pin "1") (pinfunction "PC6_1") (pintype "bidirectional"))
      (node (ref "R1") (pin "2") (pinfunction "2_2") (pintype "passive"))
    )
    (net (code "25") (name "Net-(J13-1-TRANS+)") (class "Default")
      (node (ref "J13") (pin "1") (pinfunction "1-TRANS+_1") (pintype "bidirectional"))
      (node (ref "Q2") (pin "5") (pinfunction "Y_5") (pintype "bidirectional"))
      (node (ref "R5") (pin "2") (pinfunction "2_2") (pintype "passive"))
    )
    (net (code "26") (name "Net-(J13-2-TRANS-)") (class "Default")
      (node (ref "J13") (pin "2") (pinfunction "2-TRANS-_2") (pintype "bidirectional"))
      (node (ref "Q2") (pin "6") (pinfunction "Z_6") (pintype "bidirectional"))
      (node (ref "R5") (pin "1") (pinfunction "1_1") (pintype "passive"))
    )
    (net (code "27") (name "Net-(J13-3+RECEIVE+)") (class "Default")
      (node (ref "J13") (pin "3") (pinfunction "3+RECEIVE+_3") (pintype "bidirectional"))
      (node (ref "Q2") (pin "8") (pinfunction "A_8") (pintype "bidirectional"))
      (node (ref "R6") (pin "1") (pinfunction "1_1") (pintype "passive"))
    )
    (net (code "28") (name "Net-(J13-6-RECEIVE-)") (class "Default")
      (node (ref "J13") (pin "6") (pinfunction "6-RECEIVE-_6") (pintype "bidirectional"))
      (node (ref "Q2") (pin "7") (pinfunction "B_7") (pintype "bidirectional"))
      (node (ref "R6") (pin "2") (pinfunction "2_2") (pintype "passive"))
    )
    (net (code "29") (name "Net-(Q1-AREF)") (class "Default")
      (node (ref "C5") (pin "1") (pinfunction "1_1") (pintype "passive"))
      (node (ref "Q1") (pin "21") (pinfunction "AREF_21") (pintype "bidirectional"))
    )
    (net (code "30") (name "Net-(Q1-PC2)") (class "Default")
      (node (ref "C17") (pin "1") (pinfunction "1_1") (pintype "passive"))
      (node (ref "Q1") (pin "25") (pinfunction "PC2_25") (pintype "bidirectional"))
      (node (ref "R7") (pin "2") (pinfunction "2_2") (pintype "passive"))
    )
    (net (code "31") (name "Net-(Q1-PD0)") (class "Default")
      (node (ref "Q1") (pin "2") (pinfunction "PD0_2") (pintype "bidirectional"))
      (node (ref "Q2") (pin "2") (pinfunction "R_2") (pintype "bidirectional"))
    )
    (net (code "32") (name "Net-(Q1-PD1)") (class "Default")
      (node (ref "Q1") (pin "3") (pinfunction "PD1_3") (pintype "bidirectional"))
      (node (ref "Q2") (pin "3") (pinfunction "D_3") (pintype "bidirectional"))
    )
    (net (code "33") (name "Net-(Q1-PD6)") (class "Default")
      (node (ref "Q1") (pin "12") (pinfunction "PD6_12") (pintype "bidirectional"))
      (node (ref "R8") (pin "2") (pinfunction "2_2") (pintype "passive"))
    )
    (net (code "34") (name "Net-(Q1-XTAL1)") (class "Default")
      (node (ref "C1") (pin "2") (pinfunction "2_2") (pintype "passive"))
      (node (ref "Q1") (pin "9") (pinfunction "XTAL1_9") (pintype "bidirectional"))
      (node (ref "X1") (pin "P$2") (pinfunction "2_P$2") (pintype "passive"))
    )
    (net (code "35") (name "Net-(Q1-XTAL2)") (class "Default")
      (node (ref "C2") (pin "2") (pinfunction "2_2") (pintype "passive"))
      (node (ref "Q1") (pin "10") (pinfunction "XTAL2_10") (pintype "bidirectional"))
      (node (ref "X1") (pin "P$1") (pinfunction "1_P$1") (pintype "passive"))
    )
    (net (code "36") (name "Net-(Q3-G)") (class "Default")
      (node (ref "Q3") (pin "1") (pinfunction "G_1") (pintype "bidirectional"))
      (node (ref "R4") (pin "2") (pinfunction "2_2") (pintype "passive"))
    )
    (net (code "37") (name "Net-(Q4-A)") (class "Default")
      (node (ref "Q4") (pin "10") (pinfunction "A_10") (pintype "bidirectional"))
      (node (ref "R17") (pin "2") (pinfunction "2_2") (pintype "passive"))
    )
    (net (code "38") (name "Net-(Q4-B)") (class "Default")
      (node (ref "Q4") (pin "11") (pinfunction "B_11") (pintype "bidirectional"))
      (node (ref "R18") (pin "2") (pinfunction "2_2") (pintype "passive"))
    )
    (net (code "39") (name "Net-(Q7-D)") (class "Default")
      (node (ref "Q7") (pin "2") (pinfunction "D_2") (pintype "bidirectional"))
      (node (ref "Q7") (pin "4") (pinfunction "P$1_4") (pintype "bidirectional"))
      (node (ref "Q8") (pin "4") (pinfunction "P$1_4") (pintype "bidirectional"))
    )
    (net (code "40") (name "Net-(Q9-VIOUT7)") (class "Default")
      (node (ref "Q9") (pin "7") (pinfunction "VIOUT7_7") (pintype "bidirectional"))
      (node (ref "R10") (pin "1") (pinfunction "1_1") (pintype "passive"))
    )
    (net (code "41") (name "Net-(Q20-+IN)") (class "Default")
      (node (ref "Q20") (pin "8") (pinfunction "+IN_8") (pintype "bidirectional"))
      (node (ref "R15") (pin "SENSE2") (pinfunction "SENSE2_SENSE2") (pintype "bidirectional"))
    )
    (net (code "42") (name "Net-(Q20--IN)") (class "Default")
      (node (ref "Q20") (pin "1") (pinfunction "-IN_1") (pintype "bidirectional"))
      (node (ref "R15") (pin "SENSE1") (pinfunction "SENSE1_SENSE1") (pintype "bidirectional"))
    )
    (net (code "43") (name "Net-(Q20-OUT)") (class "Default")
      (node (ref "Q20") (pin "5") (pinfunction "OUT_5") (pintype "bidirectional"))
      (node (ref "R14") (pin "1") (pinfunction "1_1") (pintype "passive"))
    )
    (net (code "44") (name "Net-(R14-Pad2)") (class "Default")
      (node (ref "R14") (pin "2") (pinfunction "2_2") (pintype "passive"))
      (node (ref "R9") (pin "1") (pinfunction "1_1") (pintype "passive"))
    )
    (net (code "45") (name "Net-(R19-Pad1)") (class "Default")
      (node (ref "R19") (pin "1") (pinfunction "1_1") (pintype "passive"))
      (node (ref "R20") (pin "2") (pinfunction "2_2") (pintype "passive"))
    )
    (net (code "46") (name "PANIC") (class "Default")
      (node (ref "J12") (pin "2") (pinfunction "2_2") (pintype "passive"))
      (node (ref "Q1") (pin "27") (pinfunction "PC4_27") (pintype "bidirectional"))
      (node (ref "R12") (pin "1") (pinfunction "1_1") (pintype "passive"))
    )
    (net (code "47") (name "QBATTERY1") (class "Default")
      (node (ref "Q10") (pin "7") (pinfunction "HO_7") (pintype "bidirectional"))
      (node (ref "Q8") (pin "1") (pinfunction "G_1") (pintype "bidirectional"))
    )
    (net (code "48") (name "QBATTERY2") (class "Default")
      (node (ref "Q11") (pin "7") (pinfunction "HO_7") (pintype "bidirectional"))
      (node (ref "Q7") (pin "1") (pinfunction "G_1") (pintype "bidirectional"))
    )
    (net (code "49") (name "S1_HIGH") (class "Default")
      (node (ref "C15") (pin "1") (pinfunction "1_1") (pintype "passive"))
      (node (ref "P2") (pin "4") (pinfunction "+VO_4") (pintype "output"))
      (node (ref "Q10") (pin "8") (pinfunction "VB_8") (pintype "bidirectional"))
    )
    (net (code "50") (name "S2_HIGH") (class "Default")
      (node (ref "C16") (pin "1") (pinfunction "1_1") (pintype "passive"))
      (node (ref "P3") (pin "4") (pinfunction "+VO_4") (pintype "output"))
      (node (ref "Q11") (pin "8") (pinfunction "VB_8") (pintype "bidirectional"))
    )
    (net (code "51") (name "S_BATTERY") (class "Default")
      (node (ref "Q1") (pin "15") (pinfunction "PB1_15") (pintype "bidirectional"))
      (node (ref "Q10") (pin "2") (pinfunction "IN_2") (pintype "bidirectional"))
      (node (ref "Q11") (pin "2") (pinfunction "IN_2") (pintype "bidirectional"))
    )
    (net (code "52") (name "S_BUCK") (class "Default")
      (node (ref "Q1") (pin "16") (pinfunction "PB2_16") (pintype "bidirectional"))
      (node (ref "Q6") (pin "2") (pinfunction "IN_2") (pintype "bidirectional"))
    )
    (net (code "53") (name "TEMP") (class "Default")
      (node (ref "Q1") (pin "28") (pinfunction "PC5_28") (pintype "bidirectional"))
      (node (ref "Q4") (pin "17") (pinfunction "YCOM_17") (pintype "bidirectional"))
    )
    (net (code "54") (name "TEMP1") (class "Default")
      (node (ref "J2") (pin "4") (pinfunction "4_4") (pintype "passive"))
      (node (ref "Q4") (pin "23") (pinfunction "Y1_23") (pintype "bidirectional"))
    )
    (net (code "55") (name "TEMP2") (class "Default")
      (node (ref "J3") (pin "4") (pinfunction "4_4") (pintype "passive"))
      (node (ref "Q4") (pin "22") (pinfunction "Y2_22") (pintype "bidirectional"))
    )
    (net (code "56") (name "TEMP3") (class "Default")
      (node (ref "J4") (pin "4") (pinfunction "4_4") (pintype "passive"))
      (node (ref "Q4") (pin "21") (pinfunction "Y3_21") (pintype "bidirectional"))
    )
    (net (code "57") (name "TEMP4") (class "Default")
      (node (ref "J5") (pin "4") (pinfunction "4_4") (pintype "passive"))
      (node (ref "Q4") (pin "20") (pinfunction "Y4_20") (pintype "bidirectional"))
    )
    (net (code "58") (name "TEMP5") (class "Default")
      (node (ref "J6") (pin "4") (pinfunction "4_4") (pintype "passive"))
      (node (ref "Q4") (pin "19") (pinfunction "Y5_19") (pintype "bidirectional"))
    )
    (net (code "59") (name "TEMP6") (class "Default")
      (node (ref "J7") (pin "4") (pinfunction "4_4") (pintype "passive"))
      (node (ref "Q4") (pin "18") (pinfunction "Y6_18") (pintype "bidirectional"))
    )
    (net (code "60") (name "TEMP7") (class "Default")
      (node (ref "J8") (pin "4") (pinfunction "4_4") (pintype "passive"))
      (node (ref "Q4") (pin "16") (pinfunction "Y7_16") (pintype "bidirectional"))
    )
    (net (code "61") (name "TEMP8") (class "Default")
      (node (ref "Q4") (pin "15") (pinfunction "Y8_15") (pintype "bidirectional"))
      (node (ref "Q5") (pin "2") (pinfunction "OUT_2") (pintype "bidirectional"))
    )
    (net (code "62") (name "VB") (class "Default")
      (node (ref "C13") (pin "1") (pinfunction "1_1") (pintype "passive"))
      (node (ref "P1") (pin "4") (pinfunction "+VO_4") (pintype "output"))
      (node (ref "Q6") (pin "8") (pinfunction "VB_8") (pintype "bidirectional"))
    )
    (net (code "63") (name "VIN") (class "Default")
      (node (ref "C27") (pin "1") (pinfunction "1_1") (pintype "passive"))
      (node (ref "Q4") (pin "2") (pinfunction "X8_2") (pintype "bidirectional"))
      (node (ref "R20") (pin "1") (pinfunction "1_1") (pintype "passive"))
      (node (ref "R21") (pin "2") (pinfunction "2_2") (pintype "passive"))
    )
    (net (code "64") (name "VOLTS") (class "Default")
      (node (ref "Q1") (pin "26") (pinfunction "PC3_26") (pintype "bidirectional"))
      (node (ref "Q4") (pin "1") (pinfunction "XCOM_1") (pintype "bidirectional"))
    )
    (net (code "65") (name "VOLTS1") (class "Default")
      (node (ref "J2") (pin "5") (pinfunction "5_5") (pintype "passive"))
      (node (ref "Q4") (pin "9") (pinfunction "X1_9") (pintype "bidirectional"))
    )
    (net (code "66") (name "VOLTS2") (class "Default")
      (node (ref "J3") (pin "5") (pinfunction "5_5") (pintype "passive"))
      (node (ref "Q4") (pin "8") (pinfunction "X2_8") (pintype "bidirectional"))
    )
    (net (code "67") (name "VOLTS3") (class "Default")
      (node (ref "J4") (pin "5") (pinfunction "5_5") (pintype "passive"))
      (node (ref "Q4") (pin "7") (pinfunction "X3_7") (pintype "bidirectional"))
    )
    (net (code "68") (name "VOLTS4") (class "Default")
      (node (ref "J5") (pin "5") (pinfunction "5_5") (pintype "passive"))
      (node (ref "Q4") (pin "6") (pinfunction "X4_6") (pintype "bidirectional"))
    )
    (net (code "69") (name "VOLTS5") (class "Default")
      (node (ref "J6") (pin "5") (pinfunction "5_5") (pintype "passive"))
      (node (ref "Q4") (pin "5") (pinfunction "X5_5") (pintype "bidirectional"))
    )
    (net (code "70") (name "VOLTS6") (class "Default")
      (node (ref "J7") (pin "5") (pinfunction "5_5") (pintype "passive"))
      (node (ref "Q4") (pin "4") (pinfunction "X6_4") (pintype "bidirectional"))
    )
    (net (code "71") (name "VOLTS7") (class "Default")
      (node (ref "J8") (pin "5") (pinfunction "5_5") (pintype "passive"))
      (node (ref "Q4") (pin "3") (pinfunction "X7_3") (pintype "bidirectional"))
    )
    (net (code "72") (name "VS") (class "Default")
      (node (ref "C13") (pin "2") (pinfunction "2_2") (pintype "passive"))
      (node (ref "D1") (pin "2") (pinfunction "C1_2") (pintype "bidirectional"))
      (node (ref "D1") (pin "4") (pinfunction "C2_4") (pintype "bidirectional"))
      (node (ref "P1") (pin "3") (pinfunction "-VO_3") (pintype "output"))
      (node (ref "Q3") (pin "3") (pinfunction "S_3") (pintype "bidirectional"))
      (node (ref "Q6") (pin "6") (pinfunction "VS_6") (pintype "bidirectional"))
      (node (ref "Q9") (pin "3") (pinfunction "IP3-_3") (pintype "bidirectional"))
      (node (ref "Q9") (pin "4") (pinfunction "IP4-_4") (pintype "bidirectional"))
    )
    (net (code "73") (name "V_MAIN") (class "Default")
      (node (ref "C12") (pin "1") (pinfunction "1_1") (pintype "passive"))
      (node (ref "Q1") (pin "23") (pinfunction "PC0_23") (pintype "bidirectional"))
      (node (ref "R2") (pin "1") (pinfunction "1_1") (pintype "passive"))
      (node (ref "R3") (pin "2") (pinfunction "2_2") (pintype "passive"))
    )
    (net (code "74") (name "unconnected-(H1-Pad1)") (class "Default")
      (node (ref "H1") (pin "1") (pinfunction "1_1") (pintype "passive"))
    )
    (net (code "75") (name "unconnected-(H2-Pad1)") (class "Default")
      (node (ref "H2") (pin "1") (pinfunction "1_1") (pintype "passive"))
    )
    (net (code "76") (name "unconnected-(H3-Pad1)") (class "Default")
      (node (ref "H3") (pin "1") (pinfunction "1_1") (pintype "passive"))
    )
    (net (code "77") (name "unconnected-(J13-4-DC+-Pad4)") (class "Default")
      (node (ref "J13") (pin "4") (pinfunction "4-DC+_4") (pintype "bidirectional"))
    )
    (net (code "78") (name "unconnected-(J13-5-DC++-Pad5)") (class "Default")
      (node (ref "J13") (pin "5") (pinfunction "5-DC++_5") (pintype "bidirectional"))
    )
    (net (code "79") (name "unconnected-(Q8-D-Pad2)") (class "Default")
      (node (ref "Q8") (pin "2") (pinfunction "D_2") (pintype "bidirectional"))
    )
    (net (code "80") (name "unconnected-(Q9-FAULT6-Pad6)") (class "Default")
      (node (ref "Q9") (pin "6") (pinfunction "FAULT6_6") (pintype "bidirectional"))
    )
  )
)
